# nRF51Socket.net
KiCad netlist of a schematic drawn in EAGLE
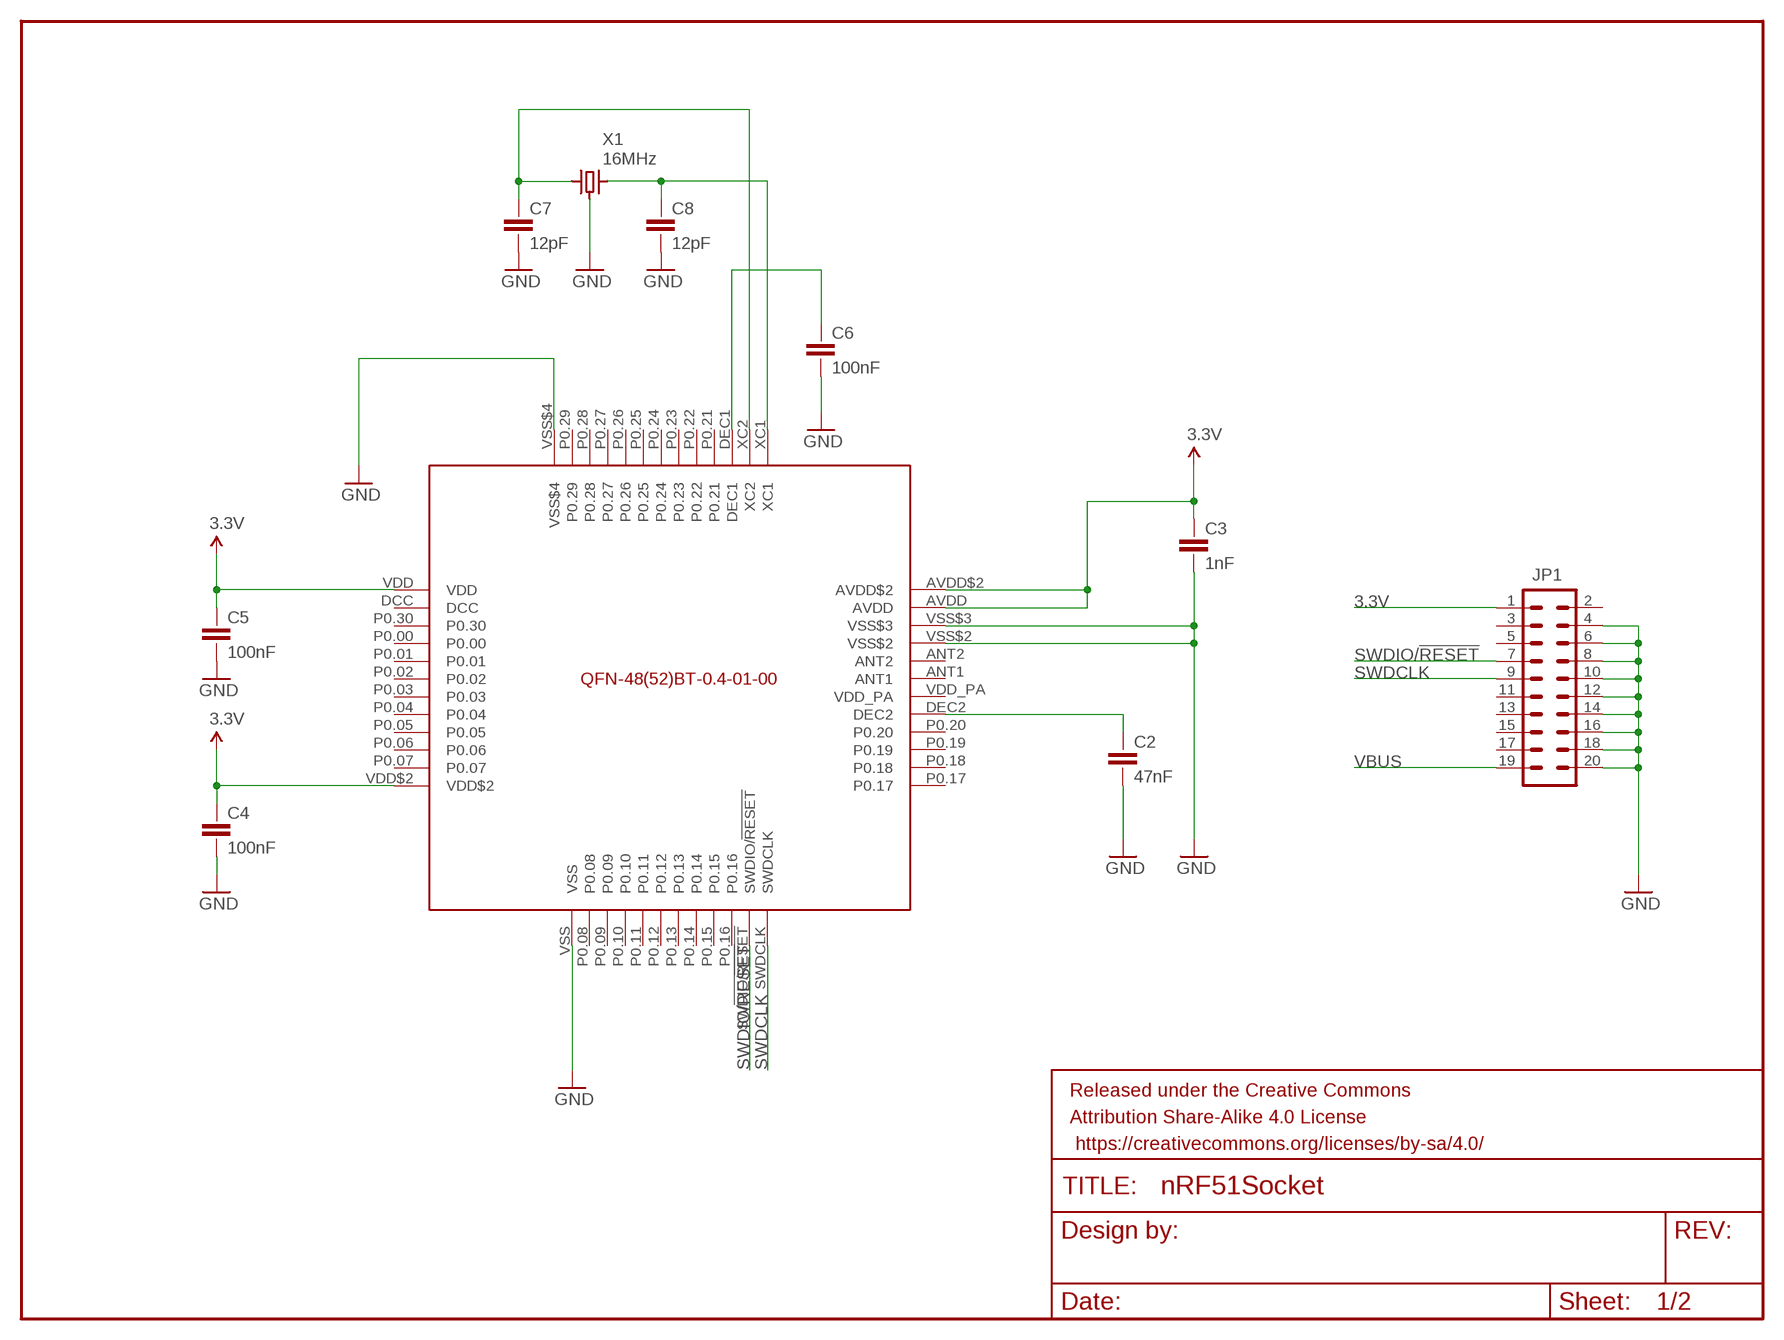
[diagram p0: schematic, sheet 1]
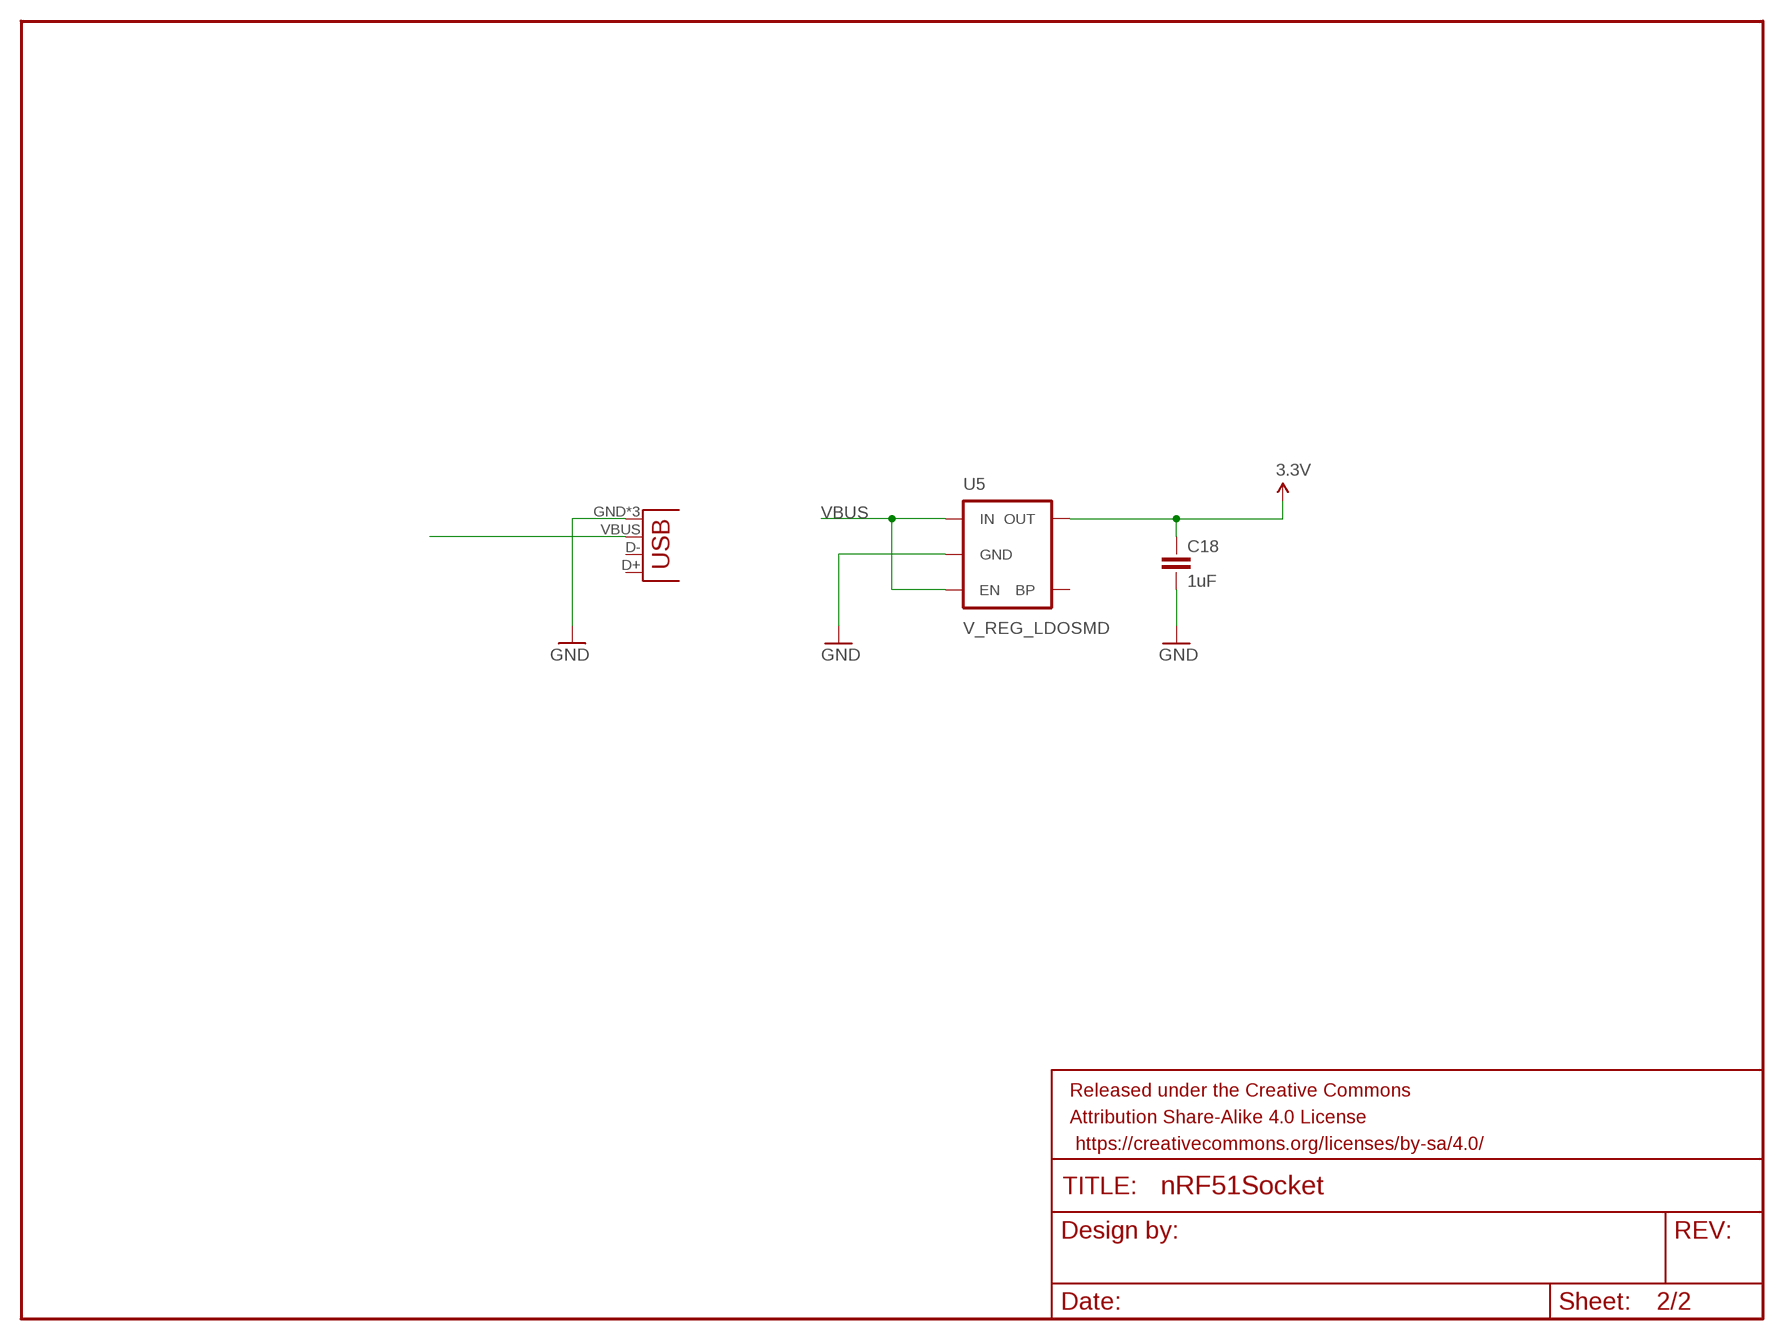
[diagram p1: schematic, sheet 2]

(export (version "E")
  (design (tool "Eeschema 10.0.6"))
  (components
    (comp (ref "C18")
      (value "1uF")
      (footprint "eagle-import:CAP-403")
      (libsource (lib "eagle-import") (part "CAP-403"))
    )
    (comp (ref "FRAME2")
      (value "FRAME-LETTERNO_PACKAGE")
      (footprint "eagle-import:DUMMY")
      (fields (field (name "DESIGNER") "Nobody"))
      (libsource (lib "eagle-import") (part "FRAME-LETTERNO_PACKAGE"))
    )
    (comp (ref "JP2")
      (value "USB-MICROB")
      (footprint "eagle-import:USB-MICROB")
      (libsource (lib "eagle-import") (part "USB-MICROB"))
    )
    (comp (ref "U5")
      (value "V_REG_LDOSMD")
      (footprint "eagle-import:SOT23-5")
      (libsource (lib "eagle-import") (part "V_REG_LDOSMD"))
    )
    (comp (ref "C2")
      (value "47nF")
      (footprint "eagle-import:CAP-403")
      (libsource (lib "eagle-import") (part "CAP-403"))
    )
    (comp (ref "C3")
      (value "1nF")
      (footprint "eagle-import:CAP-403")
      (libsource (lib "eagle-import") (part "CAP-403"))
    )
    (comp (ref "C4")
      (value "100nF")
      (footprint "eagle-import:CAP-403")
      (libsource (lib "eagle-import") (part "CAP-403"))
    )
    (comp (ref "C5")
      (value "100nF")
      (footprint "eagle-import:CAP-403")
      (libsource (lib "eagle-import") (part "CAP-403"))
    )
    (comp (ref "C6")
      (value "100nF")
      (footprint "eagle-import:CAP-403")
      (libsource (lib "eagle-import") (part "CAP-403"))
    )
    (comp (ref "C7")
      (value "12pF")
      (footprint "eagle-import:CAP-403")
      (libsource (lib "eagle-import") (part "CAP-403"))
    )
    (comp (ref "C8")
      (value "12pF")
      (footprint "eagle-import:CAP-403")
      (libsource (lib "eagle-import") (part "CAP-403"))
    )
    (comp (ref "FRAME1")
      (value "FRAME-LETTERNO_PACKAGE")
      (footprint "eagle-import:DUMMY")
      (fields (field (name "DESIGNER") "Nobody"))
      (libsource (lib "eagle-import") (part "FRAME-LETTERNO_PACKAGE"))
    )
    (comp (ref "JP1")
      (value "M10X2")
      (footprint "eagle-import:2X10")
      (libsource (lib "eagle-import") (part "M10X2"))
    )
    (comp (ref "U1")
      (value "QFN-48(52)BT-0.4-01-00")
      (footprint "eagle-import:QFN-48(52)BT-0.4-01-00")
      (libsource (lib "eagle-import") (part "QFN-48(52)BT-0.4-01-00"))
    )
    (comp (ref "X1")
      (value "16MHz")
      (footprint "eagle-import:CRYSTAL-2520")
      (libsource (lib "eagle-import") (part "CRYSTAL-GND2520"))
    )
  )
  (nets
    (net (code "1") (name "3.3V") (class "Default")
      (node (ref "C18") (pin "2") (pinfunction "1_2") (pintype "bidirectional"))
      (node (ref "C3") (pin "2") (pinfunction "1_2") (pintype "bidirectional"))
      (node (ref "C4") (pin "2") (pinfunction "1_2") (pintype "bidirectional"))
      (node (ref "C5") (pin "2") (pinfunction "1_2") (pintype "bidirectional"))
      (node (ref "JP1") (pin "1") (pinfunction "1_1") (pintype "passive"))
      (node (ref "U1") (pin "AVDD") (pinfunction "AVDD_AVDD") (pintype "bidirectional"))
      (node (ref "U1") (pin "AVDD$2") (pinfunction "AVDD$2_AVDD$2") (pintype "bidirectional"))
      (node (ref "U1") (pin "VDD") (pinfunction "VDD_VDD") (pintype "bidirectional"))
      (node (ref "U1") (pin "VDD$2") (pinfunction "VDD$2_VDD$2") (pintype "bidirectional"))
      (node (ref "U5") (pin "5") (pinfunction "OUT_5") (pintype "passive"))
    )
    (net (code "2") (name "GND") (class "Default")
      (node (ref "C18") (pin "1") (pinfunction "2_1") (pintype "bidirectional"))
      (node (ref "C2") (pin "1") (pinfunction "2_1") (pintype "bidirectional"))
      (node (ref "C3") (pin "1") (pinfunction "2_1") (pintype "bidirectional"))
      (node (ref "C4") (pin "1") (pinfunction "2_1") (pintype "bidirectional"))
      (node (ref "C5") (pin "1") (pinfunction "2_1") (pintype "bidirectional"))
      (node (ref "C6") (pin "1") (pinfunction "2_1") (pintype "bidirectional"))
      (node (ref "C7") (pin "1") (pinfunction "2_1") (pintype "bidirectional"))
      (node (ref "C8") (pin "1") (pinfunction "2_1") (pintype "bidirectional"))
      (node (ref "JP1") (pin "10") (pinfunction "10_10") (pintype "passive"))
      (node (ref "JP1") (pin "12") (pinfunction "12_12") (pintype "passive"))
      (node (ref "JP1") (pin "14") (pinfunction "14_14") (pintype "passive"))
      (node (ref "JP1") (pin "16") (pinfunction "16_16") (pintype "passive"))
      (node (ref "JP1") (pin "18") (pinfunction "18_18") (pintype "passive"))
      (node (ref "JP1") (pin "20") (pinfunction "20_20") (pintype "passive"))
      (node (ref "JP1") (pin "4") (pinfunction "4_4") (pintype "passive"))
      (node (ref "JP1") (pin "6") (pinfunction "6_6") (pintype "passive"))
      (node (ref "JP1") (pin "8") (pinfunction "8_8") (pintype "passive"))
      (node (ref "JP2") (pin "GND") (pinfunction "GND_GND") (pintype "bidirectional"))
      (node (ref "JP2") (pin "MT1") (pinfunction "GND_MT1") (pintype "bidirectional"))
      (node (ref "JP2") (pin "MT2") (pinfunction "GND_MT2") (pintype "bidirectional"))
      (node (ref "U1") (pin "VSS") (pinfunction "VSS_VSS") (pintype "bidirectional"))
      (node (ref "U1") (pin "VSS$2") (pinfunction "VSS$2_VSS$2") (pintype "bidirectional"))
      (node (ref "U1") (pin "VSS$3") (pinfunction "VSS$3_VSS$3") (pintype "bidirectional"))
      (node (ref "U1") (pin "VSS$4") (pinfunction "VSS$4_VSS$4") (pintype "bidirectional"))
      (node (ref "U5") (pin "2") (pinfunction "GND_2") (pintype "input"))
      (node (ref "X1") (pin "GND@1") (pinfunction "GND_GND@1") (pintype "bidirectional"))
      (node (ref "X1") (pin "GND@2") (pinfunction "GND_GND@2") (pintype "bidirectional"))
    )
    (net (code "3") (name "Net-(C2-1)") (class "Default")
      (node (ref "C2") (pin "2") (pinfunction "1_2") (pintype "bidirectional"))
      (node (ref "U1") (pin "DEC2") (pinfunction "DEC2_DEC2") (pintype "bidirectional"))
    )
    (net (code "4") (name "Net-(C6-1)") (class "Default")
      (node (ref "C6") (pin "2") (pinfunction "1_2") (pintype "bidirectional"))
      (node (ref "U1") (pin "DEC1") (pinfunction "DEC1_DEC1") (pintype "bidirectional"))
    )
    (net (code "5") (name "Net-(C7-1)") (class "Default")
      (node (ref "C7") (pin "2") (pinfunction "1_2") (pintype "bidirectional"))
      (node (ref "U1") (pin "XC2") (pinfunction "XC2_XC2") (pintype "bidirectional"))
      (node (ref "X1") (pin "1") (pinfunction "1_1") (pintype "bidirectional"))
    )
    (net (code "6") (name "Net-(C8-1)") (class "Default")
      (node (ref "C8") (pin "2") (pinfunction "1_2") (pintype "bidirectional"))
      (node (ref "U1") (pin "XC1") (pinfunction "XC1_XC1") (pintype "bidirectional"))
      (node (ref "X1") (pin "3") (pinfunction "3_3") (pintype "bidirectional"))
    )
    (net (code "7") (name "SWDCLK") (class "Default")
      (node (ref "JP1") (pin "9") (pinfunction "9_9") (pintype "passive"))
      (node (ref "U1") (pin "SWDCLK") (pinfunction "SWDCLK_SWDCLK") (pintype "bidirectional"))
    )
    (net (code "8") (name "SWDIO{slash}~{RESET}") (class "Default")
      (node (ref "JP1") (pin "7") (pinfunction "7_7") (pintype "passive"))
      (node (ref "U1") (pin "SWDIO/!RESET") (pinfunction "SWDIO/~{RESET}_SWDIO/!RESET") (pintype "bidirectional"))
    )
    (net (code "9") (name "VBUS") (class "Default")
      (node (ref "JP1") (pin "19") (pinfunction "19_19") (pintype "passive"))
      (node (ref "JP2") (pin "VBUS") (pinfunction "VBUS_VBUS") (pintype "bidirectional"))
      (node (ref "U5") (pin "1") (pinfunction "IN_1") (pintype "input"))
      (node (ref "U5") (pin "3") (pinfunction "EN_3") (pintype "input"))
    )
    (net (code "10") (name "unconnected-(JP1-Pad2)") (class "Default")
      (node (ref "JP1") (pin "2") (pinfunction "2_2") (pintype "passive"))
    )
    (net (code "11") (name "unconnected-(JP1-Pad3)") (class "Default")
      (node (ref "JP1") (pin "3") (pinfunction "3_3") (pintype "passive"))
    )
    (net (code "12") (name "unconnected-(JP1-Pad5)") (class "Default")
      (node (ref "JP1") (pin "5") (pinfunction "5_5") (pintype "passive"))
    )
    (net (code "13") (name "unconnected-(JP1-Pad11)") (class "Default")
      (node (ref "JP1") (pin "11") (pinfunction "11_11") (pintype "passive"))
    )
    (net (code "14") (name "unconnected-(JP1-Pad13)") (class "Default")
      (node (ref "JP1") (pin "13") (pinfunction "13_13") (pintype "passive"))
    )
    (net (code "15") (name "unconnected-(JP1-Pad15)") (class "Default")
      (node (ref "JP1") (pin "15") (pinfunction "15_15") (pintype "passive"))
    )
    (net (code "16") (name "unconnected-(JP1-Pad17)") (class "Default")
      (node (ref "JP1") (pin "17") (pinfunction "17_17") (pintype "passive"))
    )
    (net (code "17") (name "unconnected-(JP2-PadD+)") (class "Default")
      (node (ref "JP2") (pin "D+") (pinfunction "D+_D+") (pintype "bidirectional"))
    )
    (net (code "18") (name "unconnected-(JP2-PadD-)") (class "Default")
      (node (ref "JP2") (pin "D-") (pinfunction "D-_D-") (pintype "bidirectional"))
    )
    (net (code "19") (name "unconnected-(U1-PadANT1)") (class "Default")
      (node (ref "U1") (pin "ANT1") (pinfunction "ANT1_ANT1") (pintype "bidirectional"))
    )
    (net (code "20") (name "unconnected-(U1-PadANT2)") (class "Default")
      (node (ref "U1") (pin "ANT2") (pinfunction "ANT2_ANT2") (pintype "bidirectional"))
    )
    (net (code "21") (name "unconnected-(U1-PadDCC)") (class "Default")
      (node (ref "U1") (pin "DCC") (pinfunction "DCC_DCC") (pintype "bidirectional"))
    )
    (net (code "22") (name "unconnected-(U1-PadP0.00)") (class "Default")
      (node (ref "U1") (pin "P0.00") (pinfunction "P0.00_P0.00") (pintype "bidirectional"))
    )
    (net (code "23") (name "unconnected-(U1-PadP0.01)") (class "Default")
      (node (ref "U1") (pin "P0.01") (pinfunction "P0.01_P0.01") (pintype "bidirectional"))
    )
    (net (code "24") (name "unconnected-(U1-PadP0.02)") (class "Default")
      (node (ref "U1") (pin "P0.02") (pinfunction "P0.02_P0.02") (pintype "bidirectional"))
    )
    (net (code "25") (name "unconnected-(U1-PadP0.03)") (class "Default")
      (node (ref "U1") (pin "P0.03") (pinfunction "P0.03_P0.03") (pintype "bidirectional"))
    )
    (net (code "26") (name "unconnected-(U1-PadP0.04)") (class "Default")
      (node (ref "U1") (pin "P0.04") (pinfunction "P0.04_P0.04") (pintype "bidirectional"))
    )
    (net (code "27") (name "unconnected-(U1-PadP0.05)") (class "Default")
      (node (ref "U1") (pin "P0.05") (pinfunction "P0.05_P0.05") (pintype "bidirectional"))
    )
    (net (code "28") (name "unconnected-(U1-PadP0.06)") (class "Default")
      (node (ref "U1") (pin "P0.06") (pinfunction "P0.06_P0.06") (pintype "bidirectional"))
    )
    (net (code "29") (name "unconnected-(U1-PadP0.07)") (class "Default")
      (node (ref "U1") (pin "P0.07") (pinfunction "P0.07_P0.07") (pintype "bidirectional"))
    )
    (net (code "30") (name "unconnected-(U1-PadP0.08)") (class "Default")
      (node (ref "U1") (pin "P0.08") (pinfunction "P0.08_P0.08") (pintype "bidirectional"))
    )
    (net (code "31") (name "unconnected-(U1-PadP0.09)") (class "Default")
      (node (ref "U1") (pin "P0.09") (pinfunction "P0.09_P0.09") (pintype "bidirectional"))
    )
    (net (code "32") (name "unconnected-(U1-PadP0.10)") (class "Default")
      (node (ref "U1") (pin "P0.10") (pinfunction "P0.10_P0.10") (pintype "bidirectional"))
    )
    (net (code "33") (name "unconnected-(U1-PadP0.11)") (class "Default")
      (node (ref "U1") (pin "P0.11") (pinfunction "P0.11_P0.11") (pintype "bidirectional"))
    )
    (net (code "34") (name "unconnected-(U1-PadP0.12)") (class "Default")
      (node (ref "U1") (pin "P0.12") (pinfunction "P0.12_P0.12") (pintype "bidirectional"))
    )
    (net (code "35") (name "unconnected-(U1-PadP0.13)") (class "Default")
      (node (ref "U1") (pin "P0.13") (pinfunction "P0.13_P0.13") (pintype "bidirectional"))
    )
    (net (code "36") (name "unconnected-(U1-PadP0.14)") (class "Default")
      (node (ref "U1") (pin "P0.14") (pinfunction "P0.14_P0.14") (pintype "bidirectional"))
    )
    (net (code "37") (name "unconnected-(U1-PadP0.15)") (class "Default")
      (node (ref "U1") (pin "P0.15") (pinfunction "P0.15_P0.15") (pintype "bidirectional"))
    )
    (net (code "38") (name "unconnected-(U1-PadP0.16)") (class "Default")
      (node (ref "U1") (pin "P0.16") (pinfunction "P0.16_P0.16") (pintype "bidirectional"))
    )
    (net (code "39") (name "unconnected-(U1-PadP0.17)") (class "Default")
      (node (ref "U1") (pin "P0.17") (pinfunction "P0.17_P0.17") (pintype "bidirectional"))
    )
    (net (code "40") (name "unconnected-(U1-PadP0.18)") (class "Default")
      (node (ref "U1") (pin "P0.18") (pinfunction "P0.18_P0.18") (pintype "bidirectional"))
    )
    (net (code "41") (name "unconnected-(U1-PadP0.19)") (class "Default")
      (node (ref "U1") (pin "P0.19") (pinfunction "P0.19_P0.19") (pintype "bidirectional"))
    )
    (net (code "42") (name "unconnected-(U1-PadP0.20)") (class "Default")
      (node (ref "U1") (pin "P0.20") (pinfunction "P0.20_P0.20") (pintype "bidirectional"))
    )
    (net (code "43") (name "unconnected-(U1-PadP0.21)") (class "Default")
      (node (ref "U1") (pin "P0.21") (pinfunction "P0.21_P0.21") (pintype "bidirectional"))
    )
    (net (code "44") (name "unconnected-(U1-PadP0.22)") (class "Default")
      (node (ref "U1") (pin "P0.22") (pinfunction "P0.22_P0.22") (pintype "bidirectional"))
    )
    (net (code "45") (name "unconnected-(U1-PadP0.23)") (class "Default")
      (node (ref "U1") (pin "P0.23") (pinfunction "P0.23_P0.23") (pintype "bidirectional"))
    )
    (net (code "46") (name "unconnected-(U1-PadP0.24)") (class "Default")
      (node (ref "U1") (pin "P0.24") (pinfunction "P0.24_P0.24") (pintype "bidirectional"))
    )
    (net (code "47") (name "unconnected-(U1-PadP0.25)") (class "Default")
      (node (ref "U1") (pin "P0.25") (pinfunction "P0.25_P0.25") (pintype "bidirectional"))
    )
    (net (code "48") (name "unconnected-(U1-PadP0.26)") (class "Default")
      (node (ref "U1") (pin "P0.26") (pinfunction "P0.26_P0.26") (pintype "bidirectional"))
    )
    (net (code "49") (name "unconnected-(U1-PadP0.27)") (class "Default")
      (node (ref "U1") (pin "P0.27") (pinfunction "P0.27_P0.27") (pintype "bidirectional"))
    )
    (net (code "50") (name "unconnected-(U1-PadP0.28)") (class "Default")
      (node (ref "U1") (pin "P0.28") (pinfunction "P0.28_P0.28") (pintype "bidirectional"))
    )
    (net (code "51") (name "unconnected-(U1-PadP0.29)") (class "Default")
      (node (ref "U1") (pin "P0.29") (pinfunction "P0.29_P0.29") (pintype "bidirectional"))
    )
    (net (code "52") (name "unconnected-(U1-PadP0.30)") (class "Default")
      (node (ref "U1") (pin "P0.30") (pinfunction "P0.30_P0.30") (pintype "bidirectional"))
    )
    (net (code "53") (name "unconnected-(U1-PadVDD_PA)") (class "Default")
      (node (ref "U1") (pin "VDD_PA") (pinfunction "VDD_PA_VDD_PA") (pintype "bidirectional"))
    )
    (net (code "54") (name "unconnected-(U5-BP-Pad4)") (class "Default")
      (node (ref "U5") (pin "4") (pinfunction "BP_4") (pintype "input"))
    )
  )
)
